# Motor.net
KiCad netlist of a schematic drawn in Altium Designer
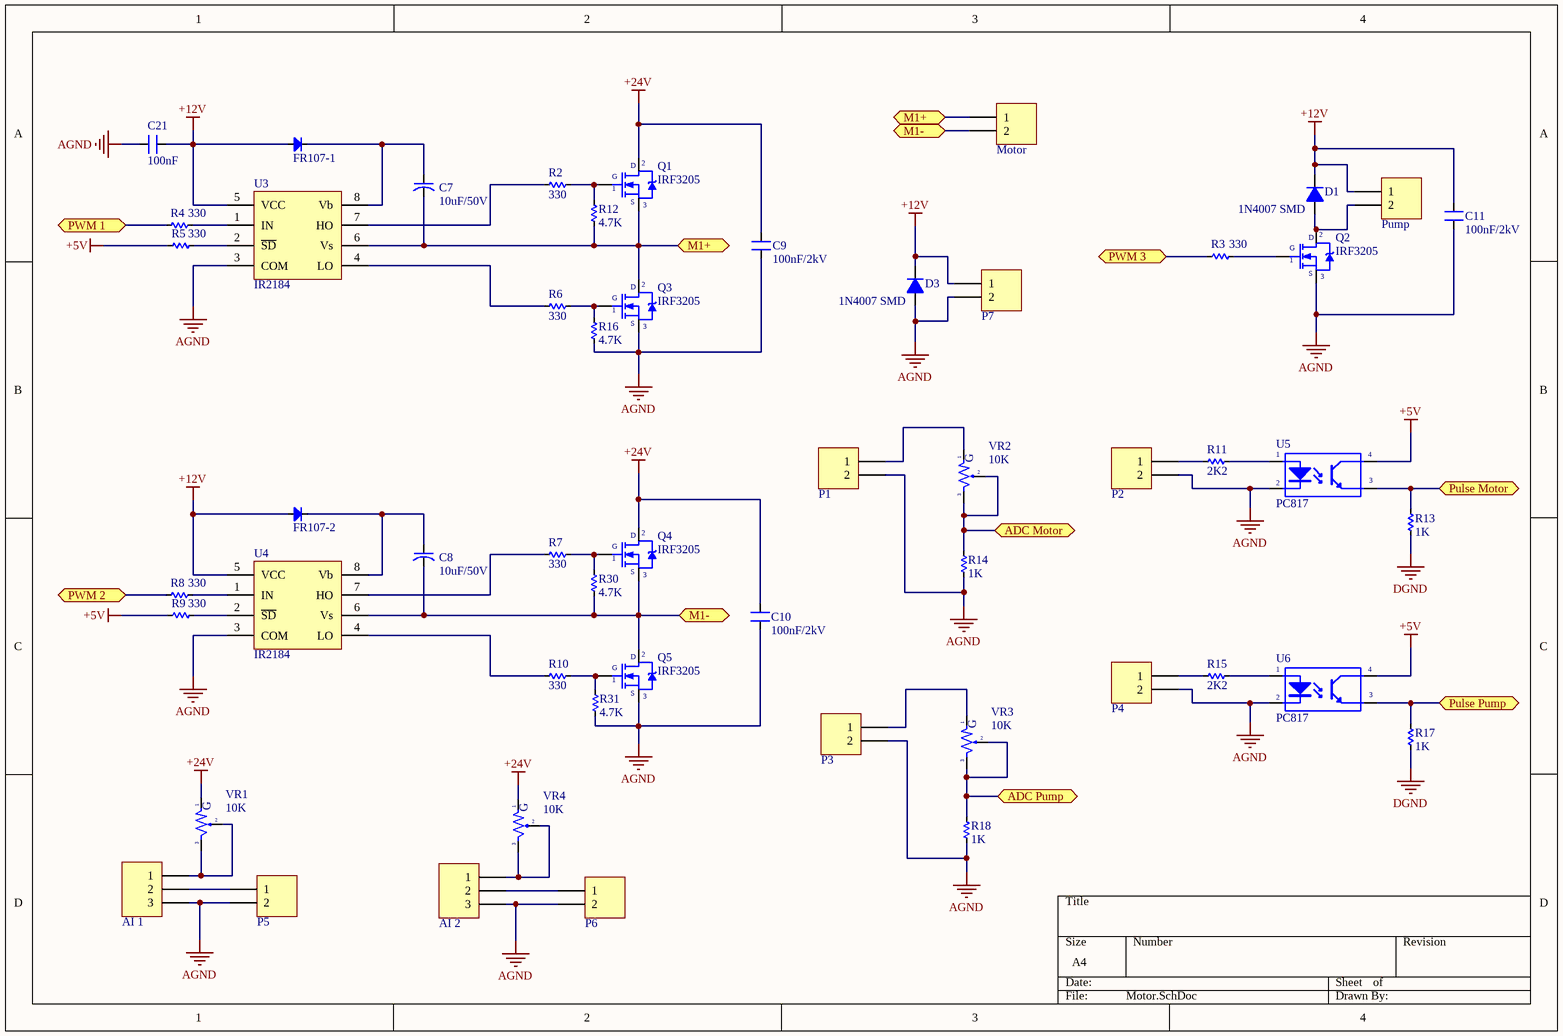
[diagram p0: Motor.SchDoc]

(export (version "E")
  (design (tool "Eeschema 10.0.6"))
  (components
    (comp (ref "AI 1")
      (value "Domino 3")
      (footprint "Header Bus 3")
      (description "Domino 3-Pin")
      (fields (field (name "PUBLISHER") "Altium Limited"))
      (libsource (lib "PIF_Schematic_Lib") (part "Domino 3"))
    )
    (comp (ref "AI 2")
      (value "Domino 3")
      (footprint "Header Bus 3")
      (description "Domino 3-Pin")
      (fields (field (name "PUBLISHER") "Altium Limited"))
      (libsource (lib "PIF_Schematic_Lib") (part "Domino 3"))
    )
    (comp (ref "C7")
      (value "10uF/50V")
      (footprint "10uF/16V")
      (description "DIP Footprint")
      (libsource (lib "BLDC_Libraries") (part "Polary Capacitor"))
    )
    (comp (ref "C8")
      (value "10uF/50V")
      (footprint "10uF/16V")
      (description "DIP Footprint")
      (libsource (lib "BLDC_Libraries") (part "Polary Capacitor"))
    )
    (comp (ref "C9")
      (value "100nF/2kV")
      (footprint "CN3")
      (description "Cap np W0.3")
      (fields (field (name "COPYRIGHT") "VanDungEvn"))
      (libsource (lib "syhaunguyen") (part "CN3"))
    )
    (comp (ref "C10")
      (value "100nF/2kV")
      (footprint "CN3")
      (description "Cap np W0.3")
      (fields (field (name "COPYRIGHT") "VanDungEvn"))
      (libsource (lib "syhaunguyen") (part "CN3"))
    )
    (comp (ref "C11")
      (value "100nF/2kV")
      (footprint "CN3")
      (description "Cap np W0.3")
      (fields (field (name "COPYRIGHT") "VanDungEvn"))
      (libsource (lib "syhaunguyen") (part "CN3"))
    )
    (comp (ref "C21") (value "100nF") (footprint "CN-SMD-0805") (libsource (lib "LIBRARY") (part "CN")))
    (comp (ref "D1")
      (value "1N4007 SMD")
      (footprint "1N4004-M4 SMD")
      (libsource (lib "BLDC_Libraries") (part "1N4004-M4 SMD"))
    )
    (comp (ref "D3")
      (value "1N4007 SMD")
      (footprint "1N4004-M4 SMD")
      (libsource (lib "BLDC_Libraries") (part "1N4004-M4 SMD"))
    )
    (comp (ref "FR107-1")
      (value "Diode")
      (footprint "SS34")
      (description "Default Diode")
      (fields (field (name "PUBLISHER") "Altium Limited"))
      (libsource (lib "LIBRARY") (part "Diode"))
    )
    (comp (ref "FR107-2")
      (value "Diode")
      (footprint "SS34")
      (description "Default Diode")
      (fields (field (name "PUBLISHER") "Altium Limited"))
      (libsource (lib "LIBRARY") (part "Diode"))
    )
    (comp (ref "Motor")
      (value "Domino 2H")
      (footprint "DOMINO 2-5mm -H")
      (description "Domino 2-Pin, Right Angle")
      (fields (field (name "PUBLISHER") "Altium Limited"))
      (libsource (lib "PIF_Schematic_Lib") (part "Domino 2H"))
    )
    (comp (ref "P1")
      (value "Domino 2")
      (footprint "Header Bus 2")
      (description "Domino, 2-Pin")
      (fields (field (name "PUBLISHER") "Altium Limited"))
      (libsource (lib "") (part "Domino 2_1"))
    )
    (comp (ref "P2")
      (value "Domino 2")
      (footprint "Header Bus 2")
      (description "Domino, 2-Pin")
      (fields (field (name "PUBLISHER") "Altium Limited"))
      (libsource (lib "") (part "Domino 2_1"))
    )
    (comp (ref "P3")
      (value "Domino 2")
      (footprint "Header Bus 2")
      (description "Domino, 2-Pin")
      (fields (field (name "PUBLISHER") "Altium Limited"))
      (libsource (lib "") (part "Domino 2_1"))
    )
    (comp (ref "P4")
      (value "Domino 2")
      (footprint "Header Bus 2")
      (description "Domino, 2-Pin")
      (fields (field (name "PUBLISHER") "Altium Limited"))
      (libsource (lib "") (part "Domino 2_1"))
    )
    (comp (ref "P5")
      (value "Domino 2")
      (footprint "Header Bus 2")
      (description "Domino, 2-Pin")
      (fields (field (name "PUBLISHER") "Altium Limited"))
      (libsource (lib "PIF_Schematic_Lib") (part "Domino 2"))
    )
    (comp (ref "P6")
      (value "Domino 2")
      (footprint "Header Bus 2")
      (description "Domino, 2-Pin")
      (fields (field (name "PUBLISHER") "Altium Limited"))
      (libsource (lib "PIF_Schematic_Lib") (part "Domino 2"))
    )
    (comp (ref "P7")
      (value "Domino 2")
      (footprint "Header Bus 2")
      (description "Domino, 2-Pin")
      (fields (field (name "PUBLISHER") "Altium Limited"))
      (libsource (lib "PIF_Schematic_Lib") (part "Domino 2"))
    )
    (comp (ref "Pump")
      (value "Domino 2H")
      (footprint "DOMINO 2-5mm -H")
      (description "Domino 2-Pin, Right Angle")
      (fields (field (name "PUBLISHER") "Altium Limited"))
      (libsource (lib "PIF_Schematic_Lib") (part "Domino 2H"))
    )
    (comp (ref "Q1")
      (value "IRF3205")
      (footprint "TO220-123")
      (description "MOSFET N - CHANNEL 500V - 0.75 - 8A - TO-220")
      (libsource (lib "LIBRARY") (part "IRF840"))
    )
    (comp (ref "Q2")
      (value "IRF3205")
      (footprint "TO220-123")
      (description "MOSFET N - CHANNEL 500V - 0.75 - 8A - TO-220")
      (libsource (lib "LIBRARY") (part "IRF840"))
    )
    (comp (ref "Q3")
      (value "IRF3205")
      (footprint "TO220-123")
      (description "MOSFET N - CHANNEL 500V - 0.75 - 8A - TO-220")
      (libsource (lib "LIBRARY") (part "IRF840"))
    )
    (comp (ref "Q4")
      (value "IRF3205")
      (footprint "TO220-123")
      (description "MOSFET N - CHANNEL 500V - 0.75 - 8A - TO-220")
      (libsource (lib "LIBRARY") (part "IRF840"))
    )
    (comp (ref "Q5")
      (value "IRF3205")
      (footprint "TO220-123")
      (description "MOSFET N - CHANNEL 500V - 0.75 - 8A - TO-220")
      (libsource (lib "LIBRARY") (part "IRF840"))
    )
    (comp (ref "R2")
      (value "330")
      (footprint "RES-SM-0805")
      (description "Res")
      (fields
        (field (name "MANUFACTURER") "Generic Components")
        (field (name "PUBLISHER") "Altium Hobart Technology Centre")
      )
      (libsource (lib "LIBRARY") (part "Res"))
    )
    (comp (ref "R3")
      (value "330")
      (footprint "RES-SM-0805")
      (description "Res")
      (fields
        (field (name "MANUFACTURER") "Generic Components")
        (field (name "PUBLISHER") "Altium Hobart Technology Centre")
      )
      (libsource (lib "LIBRARY") (part "Res"))
    )
    (comp (ref "R4")
      (value "330")
      (footprint "RES-SM-0805")
      (description "Res")
      (fields
        (field (name "MANUFACTURER") "Generic Components")
        (field (name "PUBLISHER") "Altium Hobart Technology Centre")
      )
      (libsource (lib "LIBRARY") (part "Res"))
    )
    (comp (ref "R5")
      (value "330")
      (footprint "RES-SM-0805")
      (description "Res")
      (fields
        (field (name "MANUFACTURER") "Generic Components")
        (field (name "PUBLISHER") "Altium Hobart Technology Centre")
      )
      (libsource (lib "LIBRARY") (part "Res"))
    )
    (comp (ref "R6")
      (value "330")
      (footprint "RES-SM-0805")
      (description "Res")
      (fields
        (field (name "MANUFACTURER") "Generic Components")
        (field (name "PUBLISHER") "Altium Hobart Technology Centre")
      )
      (libsource (lib "LIBRARY") (part "Res"))
    )
    (comp (ref "R7")
      (value "330")
      (footprint "RES-SM-0805")
      (description "Res")
      (fields
        (field (name "MANUFACTURER") "Generic Components")
        (field (name "PUBLISHER") "Altium Hobart Technology Centre")
      )
      (libsource (lib "LIBRARY") (part "Res"))
    )
    (comp (ref "R8")
      (value "330")
      (footprint "RES-SM-0805")
      (description "Res")
      (fields
        (field (name "MANUFACTURER") "Generic Components")
        (field (name "PUBLISHER") "Altium Hobart Technology Centre")
      )
      (libsource (lib "LIBRARY") (part "Res"))
    )
    (comp (ref "R9")
      (value "330")
      (footprint "RES-SM-0805")
      (description "Res")
      (fields
        (field (name "MANUFACTURER") "Generic Components")
        (field (name "PUBLISHER") "Altium Hobart Technology Centre")
      )
      (libsource (lib "LIBRARY") (part "Res"))
    )
    (comp (ref "R10")
      (value "330")
      (footprint "RES-SM-0805")
      (description "Res")
      (fields
        (field (name "MANUFACTURER") "Generic Components")
        (field (name "PUBLISHER") "Altium Hobart Technology Centre")
      )
      (libsource (lib "LIBRARY") (part "Res"))
    )
    (comp (ref "R11")
      (value "2K2")
      (footprint "RES-SM-0805")
      (description "Res")
      (fields
        (field (name "MANUFACTURER") "Generic Components")
        (field (name "PUBLISHER") "Altium Hobart Technology Centre")
      )
      (libsource (lib "LIBRARY") (part "Res"))
    )
    (comp (ref "R12")
      (value "4.7K")
      (footprint "RES-1/2W")
      (description "Res")
      (fields
        (field (name "MANUFACTURER") "Generic Components")
        (field (name "PUBLISHER") "Altium Hobart Technology Centre")
      )
      (libsource (lib "LIBRARY") (part "Res"))
    )
    (comp (ref "R13")
      (value "1K")
      (footprint "RES-SM-0805")
      (description "Res")
      (fields
        (field (name "MANUFACTURER") "Generic Components")
        (field (name "PUBLISHER") "Altium Hobart Technology Centre")
      )
      (libsource (lib "LIBRARY") (part "Res"))
    )
    (comp (ref "R14")
      (value "1K")
      (footprint "RES-SM-0805")
      (description "Res")
      (fields
        (field (name "MANUFACTURER") "Generic Components")
        (field (name "PUBLISHER") "Altium Hobart Technology Centre")
      )
      (libsource (lib "LIBRARY") (part "Res"))
    )
    (comp (ref "R15")
      (value "2K2")
      (footprint "RES-SM-0805")
      (description "Res")
      (fields
        (field (name "MANUFACTURER") "Generic Components")
        (field (name "PUBLISHER") "Altium Hobart Technology Centre")
      )
      (libsource (lib "LIBRARY") (part "Res"))
    )
    (comp (ref "R16")
      (value "4.7K")
      (footprint "RES-1/2W")
      (description "Res")
      (fields
        (field (name "MANUFACTURER") "Generic Components")
        (field (name "PUBLISHER") "Altium Hobart Technology Centre")
      )
      (libsource (lib "LIBRARY") (part "Res"))
    )
    (comp (ref "R17")
      (value "1K")
      (footprint "RES-SM-0805")
      (description "Res")
      (fields
        (field (name "MANUFACTURER") "Generic Components")
        (field (name "PUBLISHER") "Altium Hobart Technology Centre")
      )
      (libsource (lib "LIBRARY") (part "Res"))
    )
    (comp (ref "R18")
      (value "1K")
      (footprint "RES-SM-0805")
      (description "Res")
      (fields
        (field (name "MANUFACTURER") "Generic Components")
        (field (name "PUBLISHER") "Altium Hobart Technology Centre")
      )
      (libsource (lib "LIBRARY") (part "Res"))
    )
    (comp (ref "R30")
      (value "4.7K")
      (footprint "RES-1/2W")
      (description "Res")
      (fields
        (field (name "MANUFACTURER") "Generic Components")
        (field (name "PUBLISHER") "Altium Hobart Technology Centre")
      )
      (libsource (lib "LIBRARY") (part "Res"))
    )
    (comp (ref "R31")
      (value "4.7K")
      (footprint "RES-1/2W")
      (description "Res")
      (fields
        (field (name "MANUFACTURER") "Generic Components")
        (field (name "PUBLISHER") "Altium Hobart Technology Centre")
      )
      (libsource (lib "LIBRARY") (part "Res"))
    )
    (comp (ref "U3")
      (value "IR2184")
      (footprint "SO8")
      (description "Half-Bridge Driver")
      (libsource (lib "LIBRARY") (part "IR2184"))
    )
    (comp (ref "U4")
      (value "IR2184")
      (footprint "SO8")
      (description "Half-Bridge Driver")
      (libsource (lib "LIBRARY") (part "IR2184"))
    )
    (comp (ref "U5")
      (value "PC817")
      (footprint "DIP4")
      (description "Single Opto")
      (libsource (lib "LIBRARY") (part "PC817"))
    )
    (comp (ref "U6")
      (value "PC817")
      (footprint "DIP4")
      (description "Single Opto")
      (libsource (lib "LIBRARY") (part "PC817"))
    )
    (comp (ref "VR1")
      (value "10K")
      (footprint "VR-S2")
      (description "Var Resistor")
      (libsource (lib "LIBRARY") (part "VR-S"))
    )
    (comp (ref "VR2")
      (value "10K")
      (footprint "VR-S2")
      (description "Var Resistor")
      (libsource (lib "LIBRARY") (part "VR-S"))
    )
    (comp (ref "VR3")
      (value "10K")
      (footprint "VR-S2")
      (description "Var Resistor")
      (libsource (lib "LIBRARY") (part "VR-S"))
    )
    (comp (ref "VR4")
      (value "10K")
      (footprint "VR-S2")
      (description "Var Resistor")
      (libsource (lib "LIBRARY") (part "VR-S"))
    )
  )
  (nets
    (net (code "1") (name "+5V") (class "Default")
      (node (ref "R5") (pin "2") (pinfunction "2_2") (pintype "passive"))
      (node (ref "R9") (pin "2") (pinfunction "2_2") (pintype "passive"))
      (node (ref "U5") (pin "4") (pinfunction "C_4") (pintype "passive"))
      (node (ref "U6") (pin "4") (pinfunction "C_4") (pintype "passive"))
    )
    (net (code "2") (name "+12V") (class "Default")
      (node (ref "C11") (pin "2") (pinfunction "2_2") (pintype "passive"))
      (node (ref "C21") (pin "1") (pinfunction "1_1") (pintype "passive"))
      (node (ref "D1") (pin "1") (pinfunction "K_1") (pintype "passive"))
      (node (ref "D3") (pin "1") (pinfunction "K_1") (pintype "passive"))
      (node (ref "FR107-1") (pin "1") (pinfunction "A_1") (pintype "passive"))
      (node (ref "FR107-2") (pin "1") (pinfunction "A_1") (pintype "passive"))
      (node (ref "P7") (pin "1") (pinfunction "1_1") (pintype "passive"))
      (node (ref "Pump") (pin "1") (pinfunction "1_1") (pintype "passive"))
      (node (ref "U3") (pin "5") (pinfunction "VCC_5") (pintype "passive"))
      (node (ref "U4") (pin "5") (pinfunction "VCC_5") (pintype "passive"))
    )
    (net (code "3") (name "+24V") (class "Default")
      (node (ref "C10") (pin "2") (pinfunction "2_2") (pintype "passive"))
      (node (ref "C9") (pin "2") (pinfunction "2_2") (pintype "passive"))
      (node (ref "Q1") (pin "2") (pinfunction "D_2") (pintype "passive"))
      (node (ref "Q4") (pin "2") (pinfunction "D_2") (pintype "passive"))
      (node (ref "VR1") (pin "1") (pinfunction "1_1") (pintype "passive"))
      (node (ref "VR4") (pin "1") (pinfunction "1_1") (pintype "passive"))
    )
    (net (code "4") (name "/ADC Motor") (class "Default")
      (node (ref "R14") (pin "1") (pinfunction "1_1") (pintype "passive"))
      (node (ref "VR2") (pin "2") (pinfunction "2_2") (pintype "passive"))
      (node (ref "VR2") (pin "3") (pinfunction "3_3") (pintype "passive"))
    )
    (net (code "5") (name "/ADC Pump") (class "Default")
      (node (ref "R18") (pin "1") (pinfunction "1_1") (pintype "passive"))
      (node (ref "VR3") (pin "2") (pinfunction "2_2") (pintype "passive"))
      (node (ref "VR3") (pin "3") (pinfunction "3_3") (pintype "passive"))
    )
    (net (code "6") (name "/M1+") (class "Default")
      (node (ref "C7") (pin "2") (pinfunction "2_2") (pintype "passive"))
      (node (ref "Motor") (pin "1") (pinfunction "1_1") (pintype "passive"))
      (node (ref "Q1") (pin "3") (pinfunction "S_3") (pintype "passive"))
      (node (ref "Q3") (pin "2") (pinfunction "D_2") (pintype "passive"))
      (node (ref "R12") (pin "2") (pinfunction "2_2") (pintype "passive"))
      (node (ref "U3") (pin "6") (pinfunction "Vs_6") (pintype "passive"))
    )
    (net (code "7") (name "/M1-") (class "Default")
      (node (ref "C8") (pin "2") (pinfunction "2_2") (pintype "passive"))
      (node (ref "Motor") (pin "2") (pinfunction "2_2") (pintype "passive"))
      (node (ref "Q4") (pin "3") (pinfunction "S_3") (pintype "passive"))
      (node (ref "Q5") (pin "2") (pinfunction "D_2") (pintype "passive"))
      (node (ref "R30") (pin "2") (pinfunction "2_2") (pintype "passive"))
      (node (ref "U4") (pin "6") (pinfunction "Vs_6") (pintype "passive"))
    )
    (net (code "8") (name "/PWM 1") (class "Default")
      (node (ref "R4") (pin "2") (pinfunction "2_2") (pintype "passive"))
    )
    (net (code "9") (name "/PWM 2") (class "Default")
      (node (ref "R8") (pin "2") (pinfunction "2_2") (pintype "passive"))
    )
    (net (code "10") (name "/PWM 3") (class "Default")
      (node (ref "R3") (pin "2") (pinfunction "2_2") (pintype "passive"))
    )
    (net (code "11") (name "/Pulse Motor") (class "Default")
      (node (ref "R13") (pin "1") (pinfunction "1_1") (pintype "passive"))
      (node (ref "U5") (pin "3") (pinfunction "E_3") (pintype "passive"))
    )
    (net (code "12") (name "/Pulse Pump") (class "Default")
      (node (ref "R17") (pin "1") (pinfunction "1_1") (pintype "passive"))
      (node (ref "U6") (pin "3") (pinfunction "E_3") (pintype "passive"))
    )
    (net (code "13") (name "AGND") (class "Default")
      (node (ref "AI 1") (pin "3") (pinfunction "3_3") (pintype "passive"))
      (node (ref "AI 2") (pin "3") (pinfunction "3_3") (pintype "passive"))
      (node (ref "C10") (pin "1") (pinfunction "1_1") (pintype "passive"))
      (node (ref "C11") (pin "1") (pinfunction "1_1") (pintype "passive"))
      (node (ref "C21") (pin "2") (pinfunction "2_2") (pintype "passive"))
      (node (ref "C9") (pin "1") (pinfunction "1_1") (pintype "passive"))
      (node (ref "D3") (pin "2") (pinfunction "A_2") (pintype "passive"))
      (node (ref "P1") (pin "2") (pinfunction "2_2") (pintype "passive"))
      (node (ref "P2") (pin "2") (pinfunction "2_2") (pintype "passive"))
      (node (ref "P3") (pin "2") (pinfunction "2_2") (pintype "passive"))
      (node (ref "P4") (pin "2") (pinfunction "2_2") (pintype "passive"))
      (node (ref "P5") (pin "2") (pinfunction "2_2") (pintype "passive"))
      (node (ref "P6") (pin "2") (pinfunction "2_2") (pintype "passive"))
      (node (ref "P7") (pin "2") (pinfunction "2_2") (pintype "passive"))
      (node (ref "Q2") (pin "3") (pinfunction "S_3") (pintype "passive"))
      (node (ref "Q3") (pin "3") (pinfunction "S_3") (pintype "passive"))
      (node (ref "Q5") (pin "3") (pinfunction "S_3") (pintype "passive"))
      (node (ref "R14") (pin "2") (pinfunction "2_2") (pintype "passive"))
      (node (ref "R16") (pin "2") (pinfunction "2_2") (pintype "passive"))
      (node (ref "R18") (pin "2") (pinfunction "2_2") (pintype "passive"))
      (node (ref "R31") (pin "2") (pinfunction "2_2") (pintype "passive"))
      (node (ref "U3") (pin "3") (pinfunction "COM_3") (pintype "passive"))
      (node (ref "U4") (pin "3") (pinfunction "COM_3") (pintype "passive"))
      (node (ref "U5") (pin "2") (pinfunction "K_2") (pintype "passive"))
      (node (ref "U6") (pin "2") (pinfunction "K_2") (pintype "passive"))
    )
    (net (code "14") (name "DGND") (class "Default")
      (node (ref "R13") (pin "2") (pinfunction "2_2") (pintype "passive"))
      (node (ref "R17") (pin "2") (pinfunction "2_2") (pintype "passive"))
    )
    (net (code "15") (name "Net-(AI 1-Pad1)") (class "Default")
      (node (ref "AI 1") (pin "1") (pinfunction "1_1") (pintype "passive"))
      (node (ref "VR1") (pin "2") (pinfunction "2_2") (pintype "passive"))
      (node (ref "VR1") (pin "3") (pinfunction "3_3") (pintype "passive"))
    )
    (net (code "16") (name "Net-(AI 1-Pad2)") (class "Default")
      (node (ref "AI 1") (pin "2") (pinfunction "2_2") (pintype "passive"))
      (node (ref "P5") (pin "1") (pinfunction "1_1") (pintype "passive"))
    )
    (net (code "17") (name "Net-(AI 2-Pad1)") (class "Default")
      (node (ref "AI 2") (pin "1") (pinfunction "1_1") (pintype "passive"))
      (node (ref "VR4") (pin "2") (pinfunction "2_2") (pintype "passive"))
      (node (ref "VR4") (pin "3") (pinfunction "3_3") (pintype "passive"))
    )
    (net (code "18") (name "Net-(AI 2-Pad2)") (class "Default")
      (node (ref "AI 2") (pin "2") (pinfunction "2_2") (pintype "passive"))
      (node (ref "P6") (pin "1") (pinfunction "1_1") (pintype "passive"))
    )
    (net (code "19") (name "Net-(D1-A)") (class "Default")
      (node (ref "D1") (pin "2") (pinfunction "A_2") (pintype "passive"))
      (node (ref "Pump") (pin "2") (pinfunction "2_2") (pintype "passive"))
      (node (ref "Q2") (pin "2") (pinfunction "D_2") (pintype "passive"))
    )
    (net (code "20") (name "Net-(FR107-1-K)") (class "Default")
      (node (ref "C7") (pin "1") (pinfunction "1_1") (pintype "passive"))
      (node (ref "FR107-1") (pin "2") (pinfunction "K_2") (pintype "passive"))
      (node (ref "U3") (pin "8") (pinfunction "Vb_8") (pintype "passive"))
    )
    (net (code "21") (name "Net-(FR107-2-K)") (class "Default")
      (node (ref "C8") (pin "1") (pinfunction "1_1") (pintype "passive"))
      (node (ref "FR107-2") (pin "2") (pinfunction "K_2") (pintype "passive"))
      (node (ref "U4") (pin "8") (pinfunction "Vb_8") (pintype "passive"))
    )
    (net (code "22") (name "Net-(P1-Pad1)") (class "Default")
      (node (ref "P1") (pin "1") (pinfunction "1_1") (pintype "passive"))
      (node (ref "VR2") (pin "1") (pinfunction "1_1") (pintype "passive"))
    )
    (net (code "23") (name "Net-(P2-Pad1)") (class "Default")
      (node (ref "P2") (pin "1") (pinfunction "1_1") (pintype "passive"))
      (node (ref "R11") (pin "2") (pinfunction "2_2") (pintype "passive"))
    )
    (net (code "24") (name "Net-(P3-Pad1)") (class "Default")
      (node (ref "P3") (pin "1") (pinfunction "1_1") (pintype "passive"))
      (node (ref "VR3") (pin "1") (pinfunction "1_1") (pintype "passive"))
    )
    (net (code "25") (name "Net-(P4-Pad1)") (class "Default")
      (node (ref "P4") (pin "1") (pinfunction "1_1") (pintype "passive"))
      (node (ref "R15") (pin "2") (pinfunction "2_2") (pintype "passive"))
    )
    (net (code "26") (name "Net-(Q1-G)") (class "Default")
      (node (ref "Q1") (pin "1") (pinfunction "G_1") (pintype "passive"))
      (node (ref "R12") (pin "1") (pinfunction "1_1") (pintype "passive"))
      (node (ref "R2") (pin "1") (pinfunction "1_1") (pintype "passive"))
    )
    (net (code "27") (name "Net-(Q2-G)") (class "Default")
      (node (ref "Q2") (pin "1") (pinfunction "G_1") (pintype "passive"))
      (node (ref "R3") (pin "1") (pinfunction "1_1") (pintype "passive"))
    )
    (net (code "28") (name "Net-(Q3-G)") (class "Default")
      (node (ref "Q3") (pin "1") (pinfunction "G_1") (pintype "passive"))
      (node (ref "R16") (pin "1") (pinfunction "1_1") (pintype "passive"))
      (node (ref "R6") (pin "1") (pinfunction "1_1") (pintype "passive"))
    )
    (net (code "29") (name "Net-(Q4-G)") (class "Default")
      (node (ref "Q4") (pin "1") (pinfunction "G_1") (pintype "passive"))
      (node (ref "R30") (pin "1") (pinfunction "1_1") (pintype "passive"))
      (node (ref "R7") (pin "1") (pinfunction "1_1") (pintype "passive"))
    )
    (net (code "30") (name "Net-(Q5-G)") (class "Default")
      (node (ref "Q5") (pin "1") (pinfunction "G_1") (pintype "passive"))
      (node (ref "R10") (pin "1") (pinfunction "1_1") (pintype "passive"))
      (node (ref "R31") (pin "1") (pinfunction "1_1") (pintype "passive"))
    )
    (net (code "31") (name "Net-(U3-HO)") (class "Default")
      (node (ref "R2") (pin "2") (pinfunction "2_2") (pintype "passive"))
      (node (ref "U3") (pin "7") (pinfunction "HO_7") (pintype "passive"))
    )
    (net (code "32") (name "Net-(U3-IN)") (class "Default")
      (node (ref "R4") (pin "1") (pinfunction "1_1") (pintype "passive"))
      (node (ref "U3") (pin "1") (pinfunction "IN_1") (pintype "passive"))
    )
    (net (code "33") (name "Net-(U3-LO)") (class "Default")
      (node (ref "R6") (pin "2") (pinfunction "2_2") (pintype "passive"))
      (node (ref "U3") (pin "4") (pinfunction "LO_4") (pintype "passive"))
    )
    (net (code "34") (name "Net-(U3-~{SD})") (class "Default")
      (node (ref "R5") (pin "1") (pinfunction "1_1") (pintype "passive"))
      (node (ref "U3") (pin "2") (pinfunction "~{SD}_2") (pintype "passive"))
    )
    (net (code "35") (name "Net-(U4-HO)") (class "Default")
      (node (ref "R7") (pin "2") (pinfunction "2_2") (pintype "passive"))
      (node (ref "U4") (pin "7") (pinfunction "HO_7") (pintype "passive"))
    )
    (net (code "36") (name "Net-(U4-IN)") (class "Default")
      (node (ref "R8") (pin "1") (pinfunction "1_1") (pintype "passive"))
      (node (ref "U4") (pin "1") (pinfunction "IN_1") (pintype "passive"))
    )
    (net (code "37") (name "Net-(U4-LO)") (class "Default")
      (node (ref "R10") (pin "2") (pinfunction "2_2") (pintype "passive"))
      (node (ref "U4") (pin "4") (pinfunction "LO_4") (pintype "passive"))
    )
    (net (code "38") (name "Net-(U4-~{SD})") (class "Default")
      (node (ref "R9") (pin "1") (pinfunction "1_1") (pintype "passive"))
      (node (ref "U4") (pin "2") (pinfunction "~{SD}_2") (pintype "passive"))
    )
    (net (code "39") (name "Net-(U5-A)") (class "Default")
      (node (ref "R11") (pin "1") (pinfunction "1_1") (pintype "passive"))
      (node (ref "U5") (pin "1") (pinfunction "A_1") (pintype "passive"))
    )
    (net (code "40") (name "Net-(U6-A)") (class "Default")
      (node (ref "R15") (pin "1") (pinfunction "1_1") (pintype "passive"))
      (node (ref "U6") (pin "1") (pinfunction "A_1") (pintype "passive"))
    )
  )
)
